# MCU.net
KiCad netlist of a schematic drawn in Altium Designer
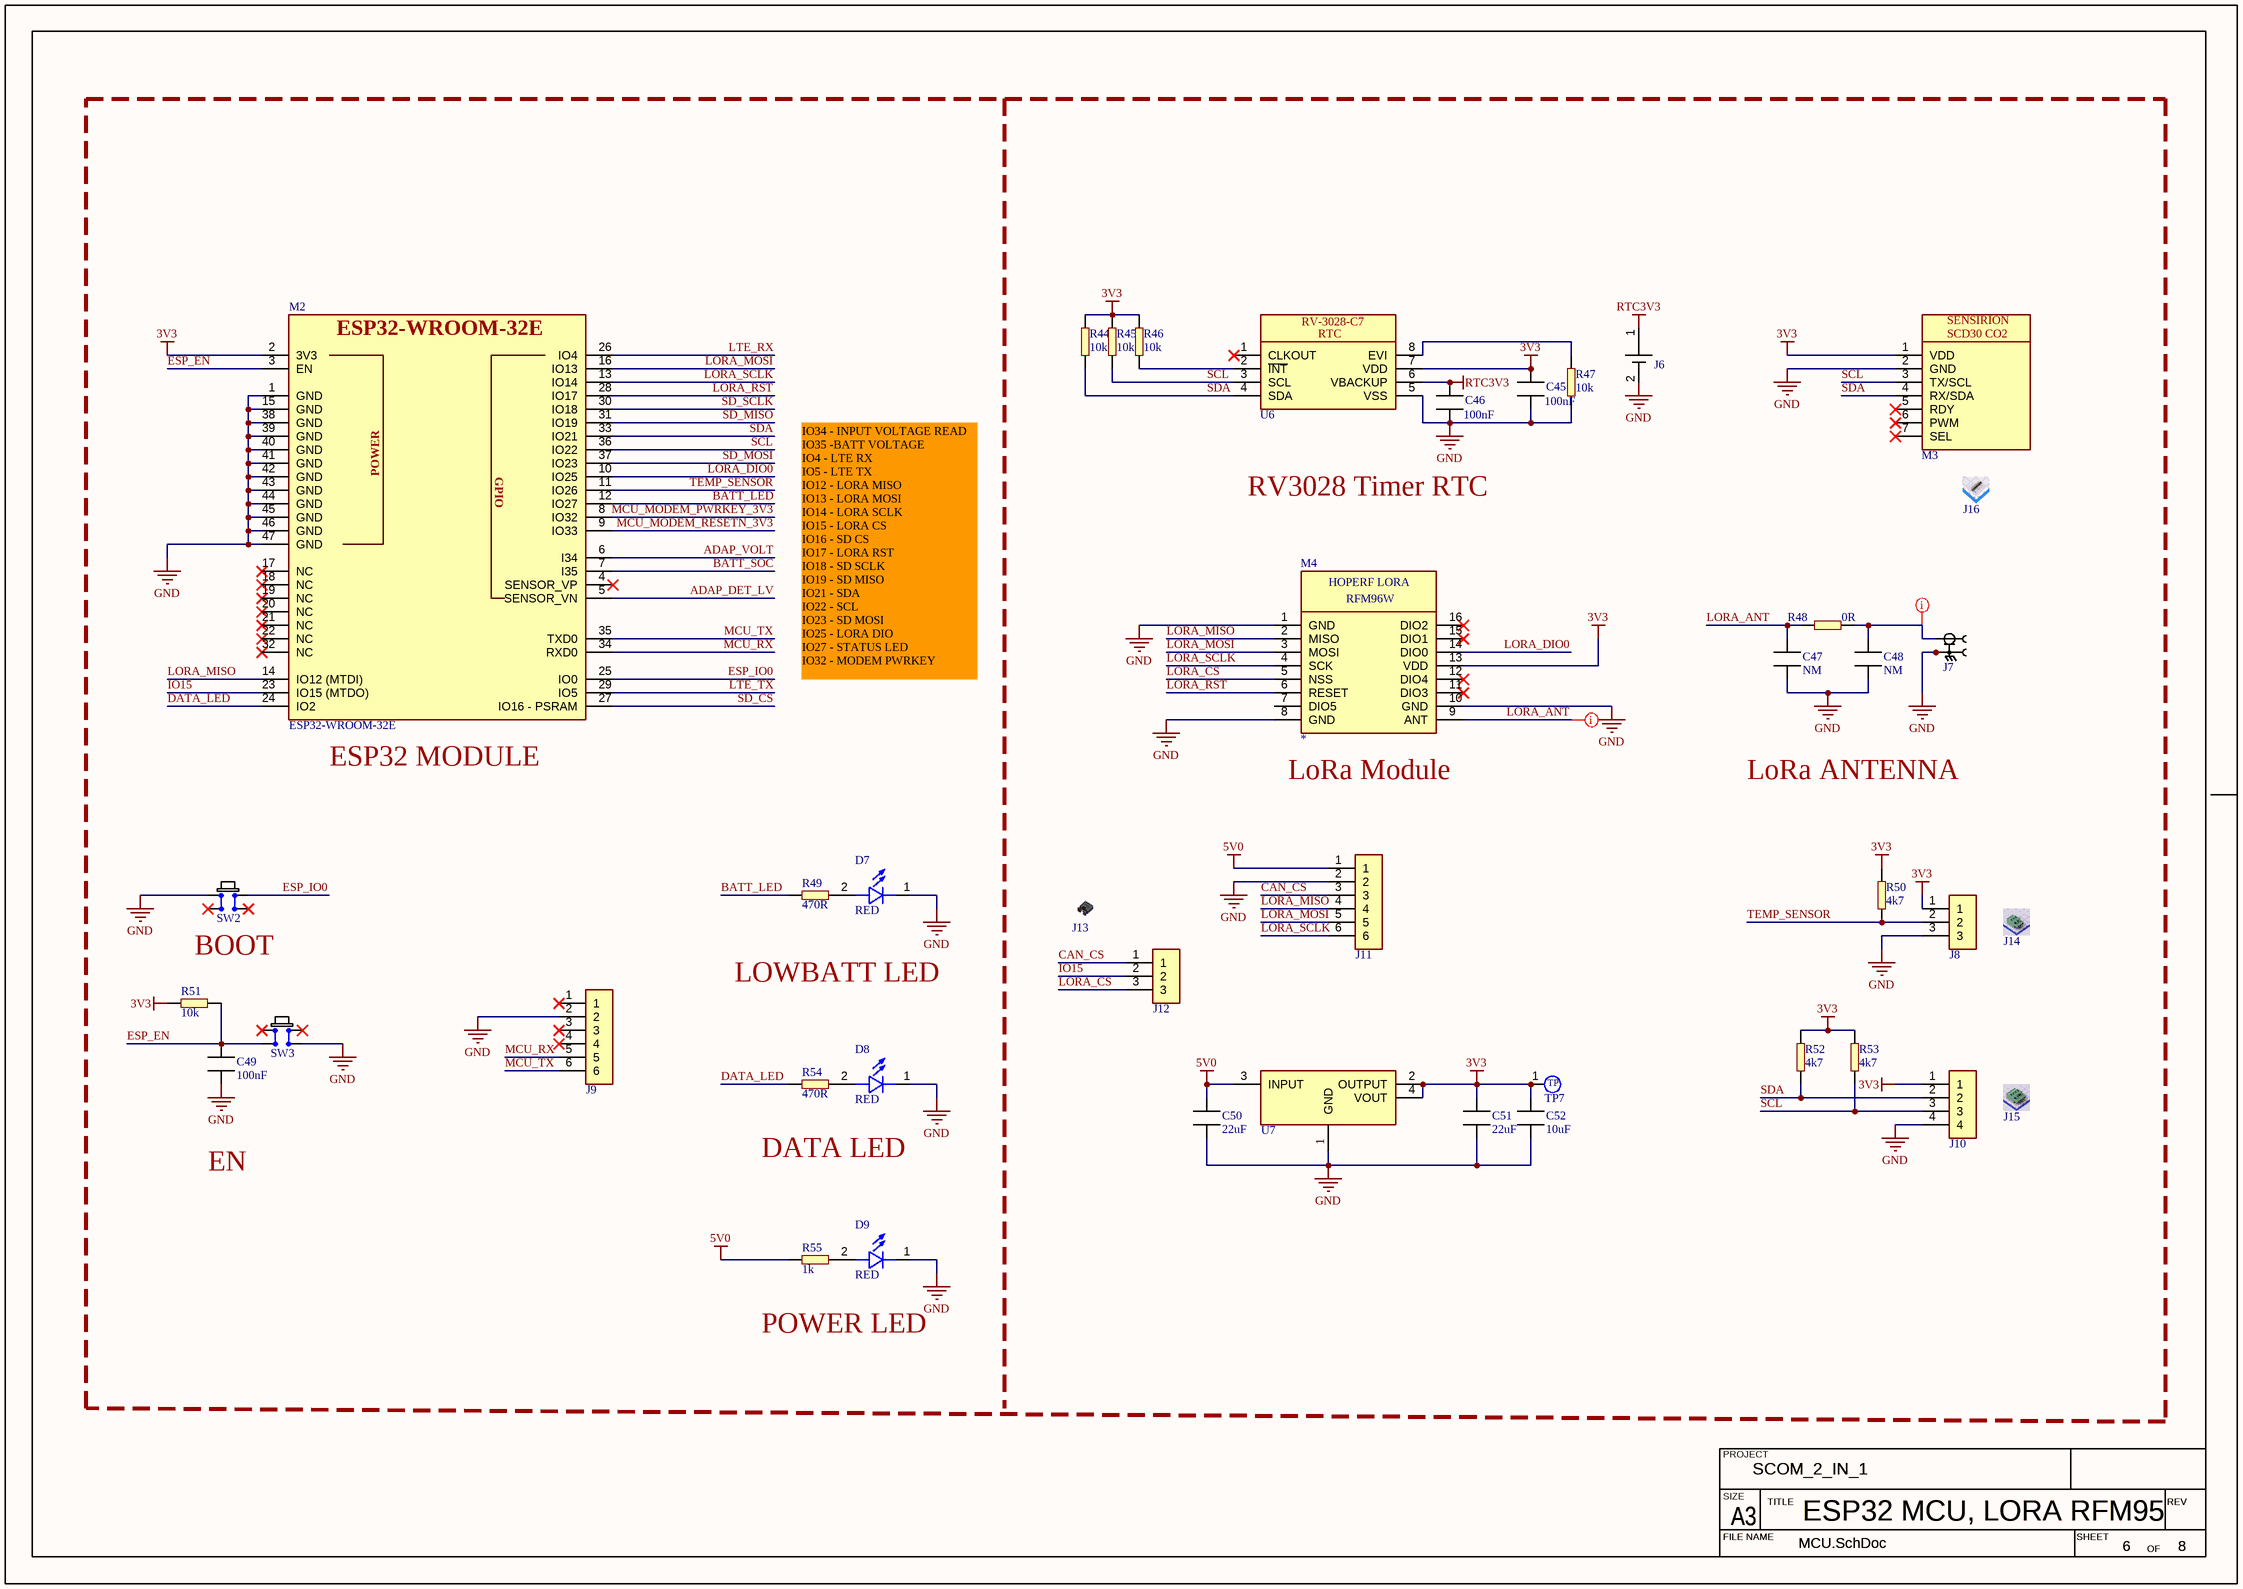
[diagram p0: MCU.SchDoc]

(export (version "E")
  (design (tool "Eeschema 10.0.6"))
  (components
    (comp (ref "C45")
      (value "100nF")
      (footprint "CAPC2012X13L")
      (description "1uF 105 0805 (2012 metric) 50V X7R MLCC SMD")
      (fields (field (name "Comment") "MLCC_0805"))
      (libsource (lib "Capacitor") (part "MLCC_0805"))
    )
    (comp (ref "C46")
      (value "100nF")
      (footprint "CAPC2012X13L")
      (description "1uF 105 0805 (2012 metric) 50V X7R MLCC SMD")
      (fields (field (name "Comment") "MLCC_0805"))
      (libsource (lib "Capacitor") (part "MLCC_0805"))
    )
    (comp (ref "C47")
      (value "NM")
      (footprint "CAPC0603X03L")
      (description "Chip Capacitor, 2-Leads, Body 0.60x0.30mm, IPC High Density")
      (fields (field (name "Comment") "ERP_102-1"))
      (libsource (lib "Capacitor") (part "MLCC_0201"))
    )
    (comp (ref "C48")
      (value "NM")
      (footprint "CAPC0603X03L")
      (description "Chip Capacitor, 2-Leads, Body 0.60x0.30mm, IPC High Density")
      (fields (field (name "Comment") "ERP_102-1"))
      (libsource (lib "Capacitor") (part "MLCC_0201"))
    )
    (comp (ref "C49")
      (value "100nF")
      (footprint "CAPC2012X13L")
      (description "Chip Capacitor, 2-Leads, Body 2.00x1.25mm, IPC High Density")
      (fields (field (name "Comment") "MLCC_0805"))
      (libsource (lib "Capacitor") (part "MLCC_0805"))
    )
    (comp (ref "C50")
      (value "22uF")
      (footprint "CAPC2012X13L")
      (description "Chip Capacitor, 2-Leads, Body 2.00x1.25mm, IPC High Density")
      (fields (field (name "Comment") "MLCC_0805"))
      (libsource (lib "Capacitor") (part "MLCC_0805"))
    )
    (comp (ref "C51")
      (value "22uF")
      (footprint "CAPC2012X13L")
      (description "Chip Capacitor, 2-Leads, Body 2.00x1.25mm, IPC High Density")
      (fields (field (name "Comment") "MLCC_0805"))
      (libsource (lib "Capacitor") (part "MLCC_0805"))
    )
    (comp (ref "C52")
      (value "10uF")
      (footprint "CAPC2012X13L")
      (description "Chip Capacitor, 2-Leads, Body 2.00x1.25mm, IPC High Density")
      (fields (field (name "Comment") "MLCC_0805"))
      (libsource (lib "Capacitor") (part "MLCC_0805"))
    )
    (comp (ref "D7")
      (value "RED")
      (footprint "LED_1206")
      (description "LED CLEAR 1206 SMD")
      (fields (field (name "Comment") "LED_1206"))
      (libsource (lib "LED") (part "LED_1206"))
    )
    (comp (ref "D8")
      (value "RED")
      (footprint "LED_1206")
      (description "LED CLEAR 1206 SMD")
      (fields (field (name "Comment") "LED_1206"))
      (libsource (lib "LED") (part "LED_1206"))
    )
    (comp (ref "D9")
      (value "RED")
      (footprint "LED_1206")
      (description "LED CLEAR 1206 SMD")
      (fields (field (name "Comment") "LED_1206"))
      (libsource (lib "LED") (part "LED_1206"))
    )
    (comp (ref "J6")
      (value "CR1220-BH")
      (footprint "CR1220-BH")
      (description "BATTERY HOLDER COIN 12.5MM SMD")
      (libsource (lib "Connectors") (part "CR1220-BH"))
    )
    (comp (ref "J7")
      (value "ERP_148-1")
      (footprint "uFL_50R")
      (description "uFL_50R")
      (libsource (lib "RF_Connector") (part "uFL_50R"))
    )
    (comp (ref "J8")
      (value "Terminal_Block_3Pin_5.08P")
      (footprint "TB_PLUG_5.08P_3P")
      (description "3PINS TERMINAL BLOCK 5.08 PITCH")
      (libsource (lib "Connectors") (part "Terminal_Block_3Pin_5.08P"))
    )
    (comp (ref "J9")
      (value "ERP_148-2")
      (footprint "6PX1R_F")
      (description "6PX1R Female Header")
      (libsource (lib "PinHeader") (part "6PX1R_F"))
    )
    (comp (ref "J10")
      (value "Terminal_Block_4Pin_5.08P")
      (footprint "TB_PLUG_5.08P_4P")
      (description "4PINS TERMINAL BLOCK 5.08 PITCH")
      (libsource (lib "Connectors") (part "Terminal_Block_4Pin_5.08P"))
    )
    (comp (ref "J11")
      (value "ERP_148-2")
      (footprint "6PX1R_F")
      (description "6PX1R Female Header")
      (libsource (lib "PinHeader") (part "6PX1R_F"))
    )
    (comp (ref "J12")
      (value "3PX1R_M")
      (footprint "3PX1R_THT")
      (description "3PX1R Male Header")
      (libsource (lib "PinHeader") (part "3PX1R_M"))
    )
    (comp (ref "J13")
      (value "Jumper Cap")
      (footprint "Jumper Cap")
      (description "2 Pin Jumper Cap P2.54")
      (libsource (lib "Jumper") (part "Jumper Cap"))
    )
    (comp (ref "J14")
      (value "SCTRM_5P08_3P")
      (footprint "SCTRM_5P08_3P")
      (description "Screw Terminal Female 3 Pin 5.08mm")
      (libsource (lib "Jumper") (part "SCTRM_5P08_3P"))
    )
    (comp (ref "J15")
      (value "SCTRM_5P08_4P")
      (footprint "SCTRM_5P08_4P")
      (description "Screw Terminal Female 4 Pin 5.08mm")
      (libsource (lib "Jumper") (part "SCTRM_5P08_4P"))
    )
    (comp (ref "J16")
      (value "PH_M_2P54_7P_RA")
      (footprint "PH_M_2P54_7P_RA")
      (description "Male Pin Header P 5.08mm 7 Pin Right Angle")
      (libsource (lib "Jumper") (part "PH_M_2P54_7P_RA"))
    )
    (comp (ref "M2")
      (value "ESP32-WROOM-32E")
      (footprint "ESP32-WROOM-32UE")
      (description "ESP32-WROOM-32E Module")
      (libsource (lib "ESP") (part "ESP32-WROOM-32E"))
    )
    (comp (ref "M3")
      (value "SCD30")
      (footprint "SCD30")
      (description "CO₂ accuracy of ±(30 ppm + 3% MV) @400-10000 ppm")
      (libsource (lib "TemperatureSensor") (part "SCD30"))
    )
    (comp (ref "M4")
      (value "RFM96W")
      (footprint "RFM96W")
      (description "LoRa 868MHz SX1276 RF Transreceiver Module RFM96W")
      (fields (field (name "ALTIUM_VALUE") "*"))
      (libsource (lib "WirelessModule") (part "RFM96W"))
    )
    (comp (ref "R44")
      (value "10k")
      (footprint "RES_0603")
      (description "RES_0603")
      (fields (field (name "Comment") "ERP_101-1"))
      (libsource (lib "") (part "RES_0603_1"))
    )
    (comp (ref "R45")
      (value "10k")
      (footprint "RES_0603")
      (description "RES_0603")
      (fields (field (name "Comment") "ERP_101-1"))
      (libsource (lib "") (part "RES_0603_1"))
    )
    (comp (ref "R46")
      (value "10k")
      (footprint "RES_0603")
      (description "RES_0603")
      (fields (field (name "Comment") "ERP_101-1"))
      (libsource (lib "") (part "RES_0603_1"))
    )
    (comp (ref "R47")
      (value "10k")
      (footprint "RES_0603")
      (description "RES_0603")
      (fields (field (name "Comment") "ERP_101-1"))
      (libsource (lib "") (part "RES_0603_1"))
    )
    (comp (ref "R48")
      (value "0R")
      (footprint "RESC0603X03L")
      (description "RES_0201")
      (fields (field (name "Comment") "ERP_101-1"))
      (libsource (lib "Resistor") (part "RES_0201"))
    )
    (comp (ref "R49")
      (value "470R")
      (footprint "RES_0603")
      (description "RES_0603")
      (fields (field (name "Comment") "ERP_101-1"))
      (libsource (lib "Resistor") (part "RES_0603"))
    )
    (comp (ref "R50")
      (value "4k7")
      (footprint "RES_0603")
      (description "RES_0603")
      (fields (field (name "Comment") "ERP_101-1"))
      (libsource (lib "") (part "RES_0603_2"))
    )
    (comp (ref "R51")
      (value "10k")
      (footprint "RES_0603")
      (description "RES_0603")
      (fields (field (name "Comment") "ERP_101-1"))
      (libsource (lib "Resistor") (part "RES_0603"))
    )
    (comp (ref "R52")
      (value "4k7")
      (footprint "RES_0603")
      (description "RES_0603")
      (fields (field (name "Comment") "ERP_101-1"))
      (libsource (lib "") (part "RES_0603_2"))
    )
    (comp (ref "R53")
      (value "4k7")
      (footprint "RES_0603")
      (description "RES_0603")
      (fields (field (name "Comment") "ERP_101-1"))
      (libsource (lib "") (part "RES_0603_2"))
    )
    (comp (ref "R54")
      (value "470R")
      (footprint "RES_0603")
      (description "RES_0603")
      (fields (field (name "Comment") "ERP_101-1"))
      (libsource (lib "Resistor") (part "RES_0603"))
    )
    (comp (ref "R55")
      (value "1k")
      (footprint "RES_0603")
      (description "RES_0603")
      (fields (field (name "Comment") "ERP_101-1"))
      (libsource (lib "Resistor") (part "RES_0603"))
    )
    (comp (ref "SW2")
      (value "Generic6X6")
      (footprint "Generic6X6")
      (description "Tactile Switch SPST-NO Top Actuated Surface Mount")
      (libsource (lib "Switch") (part "Generic6X6"))
    )
    (comp (ref "SW3")
      (value "Generic6X6")
      (footprint "Generic6X6")
      (description "Tactile Switch SPST-NO Top Actuated Surface Mount")
      (libsource (lib "Switch") (part "Generic6X6"))
    )
    (comp (ref "TP7") (value "TP_1MM") (footprint "TP_1MM") (libsource (lib "Jumper") (part "TP_1MM")))
    (comp (ref "U6")
      (value "RV-3028-C7")
      (footprint "RV-3028-C7")
      (description "IC RTC CLK/CALENDAR I2C 8SON")
      (libsource (lib "RTC") (part "RV-3028-C7"))
    )
    (comp (ref "U7")
      (value "ERP_123-1")
      (footprint "AMS1117_SOT223")
      (description "AMS1117 LDO")
      (libsource (lib "VoltageRegulator") (part "AMS1117_SOT223"))
    )
  )
  (nets
    (net (code "1") (name "/ADAP_DET_LV") (class "Default")
      (node (ref "M2") (pin "5") (pinfunction "SENSOR_VN_5") (pintype "passive"))
    )
    (net (code "2") (name "/ADAP_VOLT") (class "Default")
      (node (ref "M2") (pin "6") (pinfunction "I34_6") (pintype "passive"))
    )
    (net (code "3") (name "/BATT_LED") (class "Default")
      (node (ref "M2") (pin "12") (pinfunction "IO27_12") (pintype "passive"))
      (node (ref "R49") (pin "2") (pinfunction "2_2") (pintype "passive"))
    )
    (net (code "4") (name "/BATT_SOC") (class "Default")
      (node (ref "M2") (pin "7") (pinfunction "I35_7") (pintype "passive"))
    )
    (net (code "5") (name "/CAN_CS") (class "Default")
      (node (ref "J11") (pin "3") (pinfunction "3_3") (pintype "passive"))
      (node (ref "J12") (pin "1") (pinfunction "1_1") (pintype "passive"))
    )
    (net (code "6") (name "/DATA_LED") (class "Default")
      (node (ref "M2") (pin "24") (pinfunction "IO2_24") (pintype "passive"))
      (node (ref "R54") (pin "2") (pinfunction "2_2") (pintype "passive"))
    )
    (net (code "7") (name "/ESP_EN") (class "Default")
      (node (ref "C49") (pin "1") (pinfunction "1_1") (pintype "passive"))
      (node (ref "M2") (pin "3") (pinfunction "EN_3") (pintype "passive"))
      (node (ref "R51") (pin "1") (pinfunction "1_1") (pintype "passive"))
      (node (ref "SW3") (pin "2") (pinfunction "NO_2") (pintype "passive"))
    )
    (net (code "8") (name "/ESP_IO0") (class "Default")
      (node (ref "M2") (pin "25") (pinfunction "IO0_25") (pintype "passive"))
      (node (ref "SW2") (pin "3") (pinfunction "COM_3") (pintype "passive"))
    )
    (net (code "9") (name "/IO15") (class "Default")
      (node (ref "J12") (pin "2") (pinfunction "2_2") (pintype "passive"))
      (node (ref "M2") (pin "23") (pinfunction "IO15_(MTDO)_23") (pintype "passive"))
    )
    (net (code "10") (name "/LORA_ANT") (class "Default")
      (node (ref "C47") (pin "2") (pinfunction "2_2") (pintype "passive"))
      (node (ref "M4") (pin "9") (pinfunction "ANT_9") (pintype "passive"))
      (node (ref "R48") (pin "2") (pinfunction "2_2") (pintype "passive"))
    )
    (net (code "11") (name "/LORA_CS") (class "Default")
      (node (ref "J12") (pin "3") (pinfunction "3_3") (pintype "passive"))
      (node (ref "M4") (pin "5") (pinfunction "NSS_5") (pintype "passive"))
    )
    (net (code "12") (name "/LORA_DIO0") (class "Default")
      (node (ref "M2") (pin "10") (pinfunction "IO25_10") (pintype "passive"))
      (node (ref "M4") (pin "14") (pinfunction "DIO0_14") (pintype "passive"))
    )
    (net (code "13") (name "/LORA_MISO") (class "Default")
      (node (ref "J11") (pin "4") (pinfunction "4_4") (pintype "passive"))
      (node (ref "M2") (pin "14") (pinfunction "IO12_(MTDI)_14") (pintype "passive"))
      (node (ref "M4") (pin "2") (pinfunction "MISO_2") (pintype "passive"))
    )
    (net (code "14") (name "/LORA_MOSI") (class "Default")
      (node (ref "J11") (pin "5") (pinfunction "5_5") (pintype "passive"))
      (node (ref "M2") (pin "16") (pinfunction "IO13_16") (pintype "passive"))
      (node (ref "M4") (pin "3") (pinfunction "MOSI_3") (pintype "passive"))
    )
    (net (code "15") (name "/LORA_RST") (class "Default")
      (node (ref "M2") (pin "28") (pinfunction "IO17_28") (pintype "passive"))
      (node (ref "M4") (pin "6") (pinfunction "RESET_6") (pintype "passive"))
    )
    (net (code "16") (name "/LORA_SCLK") (class "Default")
      (node (ref "J11") (pin "6") (pinfunction "6_6") (pintype "passive"))
      (node (ref "M2") (pin "13") (pinfunction "IO14_13") (pintype "passive"))
      (node (ref "M4") (pin "4") (pinfunction "SCK_4") (pintype "passive"))
    )
    (net (code "17") (name "/LTE_RX") (class "Default")
      (node (ref "M2") (pin "26") (pinfunction "IO4_26") (pintype "passive"))
    )
    (net (code "18") (name "/LTE_TX") (class "Default")
      (node (ref "M2") (pin "29") (pinfunction "IO5_29") (pintype "passive"))
    )
    (net (code "19") (name "/MCU_MODEM_PWRKEY_3V3") (class "Default")
      (node (ref "M2") (pin "8") (pinfunction "IO32_8") (pintype "passive"))
    )
    (net (code "20") (name "/MCU_MODEM_RESETN_3V3") (class "Default")
      (node (ref "M2") (pin "9") (pinfunction "IO33_9") (pintype "passive"))
    )
    (net (code "21") (name "/MCU_RX") (class "Default")
      (node (ref "J9") (pin "5") (pinfunction "5_5") (pintype "passive"))
      (node (ref "M2") (pin "34") (pinfunction "RXD0_34") (pintype "passive"))
    )
    (net (code "22") (name "/MCU_TX") (class "Default")
      (node (ref "J9") (pin "6") (pinfunction "6_6") (pintype "passive"))
      (node (ref "M2") (pin "35") (pinfunction "TXD0_35") (pintype "passive"))
    )
    (net (code "23") (name "/SCL") (class "Default")
      (node (ref "J10") (pin "3") (pinfunction "3_3") (pintype "passive"))
      (node (ref "M2") (pin "36") (pinfunction "IO22_36") (pintype "passive"))
      (node (ref "M3") (pin "3") (pinfunction "TX/SCL_3") (pintype "passive"))
      (node (ref "R45") (pin "1") (pinfunction "1_1") (pintype "passive"))
      (node (ref "R53") (pin "2") (pinfunction "2_2") (pintype "passive"))
      (node (ref "U6") (pin "3") (pinfunction "SCL_3") (pintype "passive"))
    )
    (net (code "24") (name "/SDA") (class "Default")
      (node (ref "J10") (pin "2") (pinfunction "2_2") (pintype "passive"))
      (node (ref "M2") (pin "33") (pinfunction "IO21_33") (pintype "passive"))
      (node (ref "M3") (pin "4") (pinfunction "RX/SDA_4") (pintype "passive"))
      (node (ref "R44") (pin "1") (pinfunction "1_1") (pintype "passive"))
      (node (ref "R52") (pin "2") (pinfunction "2_2") (pintype "passive"))
      (node (ref "U6") (pin "4") (pinfunction "SDA_4") (pintype "passive"))
    )
    (net (code "25") (name "/SD_CS") (class "Default")
      (node (ref "M2") (pin "27") (pinfunction "IO16_-_PSRAM_27") (pintype "passive"))
    )
    (net (code "26") (name "/SD_MISO") (class "Default")
      (node (ref "M2") (pin "31") (pinfunction "IO19_31") (pintype "passive"))
    )
    (net (code "27") (name "/SD_MOSI") (class "Default")
      (node (ref "M2") (pin "37") (pinfunction "IO23_37") (pintype "passive"))
    )
    (net (code "28") (name "/SD_SCLK") (class "Default")
      (node (ref "M2") (pin "30") (pinfunction "IO18_30") (pintype "passive"))
    )
    (net (code "29") (name "/TEMP_SENSOR") (class "Default")
      (node (ref "J8") (pin "2") (pinfunction "2_2") (pintype "passive"))
      (node (ref "M2") (pin "11") (pinfunction "IO26_11") (pintype "passive"))
      (node (ref "R50") (pin "2") (pinfunction "2_2") (pintype "passive"))
    )
    (net (code "30") (name "3V3") (class "Default")
      (node (ref "C45") (pin "1") (pinfunction "1_1") (pintype "passive"))
      (node (ref "C51") (pin "1") (pinfunction "1_1") (pintype "passive"))
      (node (ref "C52") (pin "1") (pinfunction "1_1") (pintype "passive"))
      (node (ref "J10") (pin "1") (pinfunction "1_1") (pintype "passive"))
      (node (ref "J8") (pin "1") (pinfunction "1_1") (pintype "passive"))
      (node (ref "M2") (pin "2") (pinfunction "3V3_2") (pintype "passive"))
      (node (ref "M3") (pin "1") (pinfunction "VDD_1") (pintype "passive"))
      (node (ref "M4") (pin "13") (pinfunction "VDD_13") (pintype "passive"))
      (node (ref "R44") (pin "2") (pinfunction "2_2") (pintype "passive"))
      (node (ref "R45") (pin "2") (pinfunction "2_2") (pintype "passive"))
      (node (ref "R46") (pin "2") (pinfunction "2_2") (pintype "passive"))
      (node (ref "R50") (pin "1") (pinfunction "1_1") (pintype "passive"))
      (node (ref "R51") (pin "2") (pinfunction "2_2") (pintype "passive"))
      (node (ref "R52") (pin "1") (pinfunction "1_1") (pintype "passive"))
      (node (ref "R53") (pin "1") (pinfunction "1_1") (pintype "passive"))
      (node (ref "TP7") (pin "1") (pinfunction "1_1") (pintype "passive"))
      (node (ref "U6") (pin "7") (pinfunction "VDD_7") (pintype "passive"))
      (node (ref "U7") (pin "2") (pinfunction "OUTPUT_2") (pintype "passive"))
      (node (ref "U7") (pin "4") (pinfunction "VOUT_4") (pintype "passive"))
    )
    (net (code "31") (name "5V0") (class "Default")
      (node (ref "C50") (pin "1") (pinfunction "1_1") (pintype "passive"))
      (node (ref "J11") (pin "1") (pinfunction "1_1") (pintype "passive"))
      (node (ref "R55") (pin "2") (pinfunction "2_2") (pintype "passive"))
      (node (ref "U7") (pin "3") (pinfunction "INPUT_3") (pintype "passive"))
    )
    (net (code "32") (name "GND") (class "Default")
      (node (ref "C45") (pin "2") (pinfunction "2_2") (pintype "passive"))
      (node (ref "C46") (pin "2") (pinfunction "2_2") (pintype "passive"))
      (node (ref "C47") (pin "1") (pinfunction "1_1") (pintype "passive"))
      (node (ref "C48") (pin "1") (pinfunction "1_1") (pintype "passive"))
      (node (ref "C49") (pin "2") (pinfunction "2_2") (pintype "passive"))
      (node (ref "C50") (pin "2") (pinfunction "2_2") (pintype "passive"))
      (node (ref "C51") (pin "2") (pinfunction "2_2") (pintype "passive"))
      (node (ref "C52") (pin "2") (pinfunction "2_2") (pintype "passive"))
      (node (ref "D7") (pin "1") (pinfunction "1_1") (pintype "passive"))
      (node (ref "D8") (pin "1") (pinfunction "1_1") (pintype "passive"))
      (node (ref "D9") (pin "1") (pinfunction "1_1") (pintype "passive"))
      (node (ref "J10") (pin "4") (pinfunction "4_4") (pintype "passive"))
      (node (ref "J11") (pin "2") (pinfunction "2_2") (pintype "passive"))
      (node (ref "J6") (pin "2") (pinfunction "-_2") (pintype "passive"))
      (node (ref "J7") (pin "1") (pinfunction "1_1") (pintype "passive"))
      (node (ref "J7") (pin "2") (pinfunction "2_2") (pintype "passive"))
      (node (ref "J8") (pin "3") (pinfunction "3_3") (pintype "passive"))
      (node (ref "J9") (pin "2") (pinfunction "2_2") (pintype "passive"))
      (node (ref "M2") (pin "1") (pinfunction "GND_1") (pintype "passive"))
      (node (ref "M2") (pin "15") (pinfunction "GND_15") (pintype "passive"))
      (node (ref "M2") (pin "38") (pinfunction "GND_38") (pintype "passive"))
      (node (ref "M2") (pin "39") (pinfunction "GND_39") (pintype "passive"))
      (node (ref "M2") (pin "40") (pinfunction "GND_40") (pintype "passive"))
      (node (ref "M2") (pin "41") (pinfunction "GND_41") (pintype "passive"))
      (node (ref "M2") (pin "42") (pinfunction "GND_42") (pintype "passive"))
      (node (ref "M2") (pin "43") (pinfunction "GND_43") (pintype "passive"))
      (node (ref "M2") (pin "44") (pinfunction "GND_44") (pintype "passive"))
      (node (ref "M2") (pin "45") (pinfunction "GND_45") (pintype "passive"))
      (node (ref "M2") (pin "46") (pinfunction "GND_46") (pintype "passive"))
      (node (ref "M2") (pin "47") (pinfunction "GND_47") (pintype "passive"))
      (node (ref "M3") (pin "2") (pinfunction "GND_2") (pintype "passive"))
      (node (ref "M4") (pin "1") (pinfunction "GND_1") (pintype "passive"))
      (node (ref "M4") (pin "10") (pinfunction "GND_10") (pintype "passive"))
      (node (ref "M4") (pin "8") (pinfunction "GND_8") (pintype "passive"))
      (node (ref "R47") (pin "1") (pinfunction "1_1") (pintype "passive"))
      (node (ref "SW2") (pin "1") (pinfunction "NO_1") (pintype "passive"))
      (node (ref "SW3") (pin "4") (pinfunction "COM_4") (pintype "passive"))
      (node (ref "U6") (pin "5") (pinfunction "VSS_5") (pintype "passive"))
      (node (ref "U7") (pin "1") (pinfunction "GND_1") (pintype "power_in"))
    )
    (net (code "33") (name "Net-(C48-Pad2)") (class "Default")
      (node (ref "C48") (pin "2") (pinfunction "2_2") (pintype "passive"))
      (node (ref "J7") (pin "3") (pinfunction "3_3") (pintype "passive"))
      (node (ref "R48") (pin "1") (pinfunction "1_1") (pintype "passive"))
    )
    (net (code "34") (name "Net-(D7-Pad2)") (class "Default")
      (node (ref "D7") (pin "2") (pinfunction "2_2") (pintype "passive"))
      (node (ref "R49") (pin "1") (pinfunction "1_1") (pintype "passive"))
    )
    (net (code "35") (name "Net-(D8-Pad2)") (class "Default")
      (node (ref "D8") (pin "2") (pinfunction "2_2") (pintype "passive"))
      (node (ref "R54") (pin "1") (pinfunction "1_1") (pintype "passive"))
    )
    (net (code "36") (name "Net-(D9-Pad2)") (class "Default")
      (node (ref "D9") (pin "2") (pinfunction "2_2") (pintype "passive"))
      (node (ref "R55") (pin "1") (pinfunction "1_1") (pintype "passive"))
    )
    (net (code "37") (name "Net-(U6-EVI)") (class "Default")
      (node (ref "R47") (pin "2") (pinfunction "2_2") (pintype "passive"))
      (node (ref "U6") (pin "8") (pinfunction "EVI_8") (pintype "passive"))
    )
    (net (code "38") (name "Net-(U6-~{INT})") (class "Default")
      (node (ref "R46") (pin "1") (pinfunction "1_1") (pintype "passive"))
      (node (ref "U6") (pin "2") (pinfunction "~{INT}_2") (pintype "passive"))
    )
    (net (code "39") (name "RTC3V3") (class "Default")
      (node (ref "C46") (pin "1") (pinfunction "1_1") (pintype "passive"))
      (node (ref "J6") (pin "1") (pinfunction "+_1") (pintype "passive"))
      (node (ref "U6") (pin "6") (pinfunction "VBACKUP_6") (pintype "passive"))
    )
    (net (code "40") (name "unconnected-(J9-Pad1)") (class "Default")
      (node (ref "J9") (pin "1") (pinfunction "1_1") (pintype "passive+no_connect"))
    )
    (net (code "41") (name "unconnected-(J9-Pad3)") (class "Default")
      (node (ref "J9") (pin "3") (pinfunction "3_3") (pintype "passive+no_connect"))
    )
    (net (code "42") (name "unconnected-(J9-Pad4)") (class "Default")
      (node (ref "J9") (pin "4") (pinfunction "4_4") (pintype "passive+no_connect"))
    )
    (net (code "43") (name "unconnected-(M2-NC-Pad17)") (class "Default")
      (node (ref "M2") (pin "17") (pinfunction "NC_17") (pintype "passive+no_connect"))
    )
    (net (code "44") (name "unconnected-(M2-NC-Pad18)") (class "Default")
      (node (ref "M2") (pin "18") (pinfunction "NC_18") (pintype "passive+no_connect"))
    )
    (net (code "45") (name "unconnected-(M2-NC-Pad19)") (class "Default")
      (node (ref "M2") (pin "19") (pinfunction "NC_19") (pintype "passive+no_connect"))
    )
    (net (code "46") (name "unconnected-(M2-NC-Pad20)") (class "Default")
      (node (ref "M2") (pin "20") (pinfunction "NC_20") (pintype "passive+no_connect"))
    )
    (net (code "47") (name "unconnected-(M2-NC-Pad21)") (class "Default")
      (node (ref "M2") (pin "21") (pinfunction "NC_21") (pintype "passive+no_connect"))
    )
    (net (code "48") (name "unconnected-(M2-NC-Pad22)") (class "Default")
      (node (ref "M2") (pin "22") (pinfunction "NC_22") (pintype "passive+no_connect"))
    )
    (net (code "49") (name "unconnected-(M2-NC-Pad32)") (class "Default")
      (node (ref "M2") (pin "32") (pinfunction "NC_32") (pintype "passive+no_connect"))
    )
    (net (code "50") (name "unconnected-(M2-SENSOR_VP-Pad4)") (class "Default")
      (node (ref "M2") (pin "4") (pinfunction "SENSOR_VP_4") (pintype "passive+no_connect"))
    )
    (net (code "51") (name "unconnected-(M3-PWM-Pad6)") (class "Default")
      (node (ref "M3") (pin "6") (pinfunction "PWM_6") (pintype "passive+no_connect"))
    )
    (net (code "52") (name "unconnected-(M3-RDY-Pad5)") (class "Default")
      (node (ref "M3") (pin "5") (pinfunction "RDY_5") (pintype "passive+no_connect"))
    )
    (net (code "53") (name "unconnected-(M3-SEL-Pad7)") (class "Default")
      (node (ref "M3") (pin "7") (pinfunction "SEL_7") (pintype "passive+no_connect"))
    )
    (net (code "54") (name "unconnected-(M4-DIO1-Pad15)") (class "Default")
      (node (ref "M4") (pin "15") (pinfunction "DIO1_15") (pintype "passive+no_connect"))
    )
    (net (code "55") (name "unconnected-(M4-DIO2-Pad16)") (class "Default")
      (node (ref "M4") (pin "16") (pinfunction "DIO2_16") (pintype "passive+no_connect"))
    )
    (net (code "56") (name "unconnected-(M4-DIO3-Pad11)") (class "Default")
      (node (ref "M4") (pin "11") (pinfunction "DIO3_11") (pintype "passive+no_connect"))
    )
    (net (code "57") (name "unconnected-(M4-DIO4-Pad12)") (class "Default")
      (node (ref "M4") (pin "12") (pinfunction "DIO4_12") (pintype "passive+no_connect"))
    )
    (net (code "58") (name "unconnected-(M4-DIO5-Pad7)") (class "Default")
      (node (ref "M4") (pin "7") (pinfunction "DIO5_7") (pintype "passive"))
    )
    (net (code "59") (name "unconnected-(SW2-COM-Pad4)") (class "Default")
      (node (ref "SW2") (pin "4") (pinfunction "COM_4") (pintype "passive+no_connect"))
    )
    (net (code "60") (name "unconnected-(SW2-NO-Pad2)") (class "Default")
      (node (ref "SW2") (pin "2") (pinfunction "NO_2") (pintype "passive+no_connect"))
    )
    (net (code "61") (name "unconnected-(SW3-COM-Pad3)") (class "Default")
      (node (ref "SW3") (pin "3") (pinfunction "COM_3") (pintype "passive+no_connect"))
    )
    (net (code "62") (name "unconnected-(SW3-NO-Pad1)") (class "Default")
      (node (ref "SW3") (pin "1") (pinfunction "NO_1") (pintype "passive+no_connect"))
    )
    (net (code "63") (name "unconnected-(U6-CLKOUT-Pad1)") (class "Default")
      (node (ref "U6") (pin "1") (pinfunction "CLKOUT_1") (pintype "passive+no_connect"))
    )
  )
)
